# mcp23008.net
KiCad netlist of a schematic drawn in EAGLE
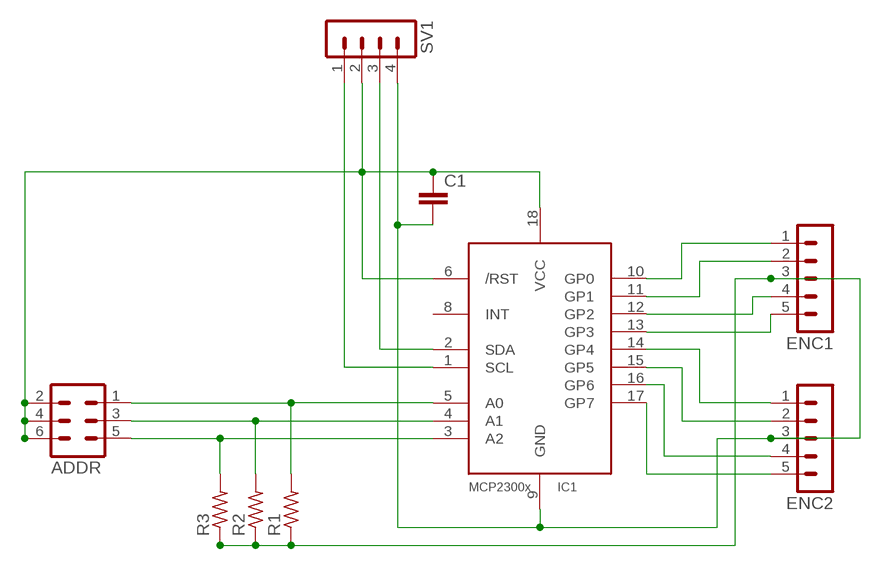
[diagram p0: schematic, sheet 1]

(export (version "E")
  (design (tool "Eeschema 10.0.6"))
  (components
    (comp (ref "ADDR")
      (value "MA03-2")
      (footprint "eagle-import:MA03-2")
      (libsource (lib "eagle-import") (part "MA03-2"))
    )
    (comp (ref "C1")
      (value "C2.5/2")
      (footprint "eagle-import:C2.5-2")
      (libsource (lib "eagle-import") (part "C2.5/2"))
    )
    (comp (ref "ENC1")
      (value "MA05-1")
      (footprint "eagle-import:MA05-1")
      (libsource (lib "eagle-import") (part "MA05-1"))
    )
    (comp (ref "ENC2")
      (value "MA05-1")
      (footprint "eagle-import:MA05-1")
      (libsource (lib "eagle-import") (part "MA05-1"))
    )
    (comp (ref "IC1")
      (value "MCP2300X/P")
      (footprint "eagle-import:DIL18")
      (libsource (lib "eagle-import") (part "MCP2300X/P"))
    )
    (comp (ref "R1")
      (value "R-US_0204/7")
      (footprint "eagle-import:0204_7")
      (libsource (lib "eagle-import") (part "R-US_0204/7"))
    )
    (comp (ref "R2")
      (value "R-US_0204/7")
      (footprint "eagle-import:0204_7")
      (libsource (lib "eagle-import") (part "R-US_0204/7"))
    )
    (comp (ref "R3")
      (value "R-US_0204/7")
      (footprint "eagle-import:0204_7")
      (libsource (lib "eagle-import") (part "R-US_0204/7"))
    )
    (comp (ref "SV1")
      (value "MA04-1")
      (footprint "eagle-import:MA04-1")
      (libsource (lib "eagle-import") (part "MA04-1"))
    )
  )
  (nets
    (net (code "1") (name "Net-(IC1-A0)") (class "Default")
      (node (ref "ADDR") (pin "1") (pinfunction "1_1") (pintype "passive"))
      (node (ref "IC1") (pin "5") (pinfunction "A0_5") (pintype "input"))
      (node (ref "R1") (pin "2") (pinfunction "2_2") (pintype "passive"))
    )
    (net (code "2") (name "Net-(IC1-A1)") (class "Default")
      (node (ref "ADDR") (pin "3") (pinfunction "3_3") (pintype "passive"))
      (node (ref "IC1") (pin "4") (pinfunction "A1_4") (pintype "input"))
      (node (ref "R2") (pin "2") (pinfunction "2_2") (pintype "passive"))
    )
    (net (code "3") (name "Net-(IC1-A2)") (class "Default")
      (node (ref "ADDR") (pin "5") (pinfunction "5_5") (pintype "passive"))
      (node (ref "IC1") (pin "3") (pinfunction "A2_3") (pintype "input"))
      (node (ref "R3") (pin "2") (pinfunction "2_2") (pintype "passive"))
    )
    (net (code "4") (name "Net-(IC1-GND)") (class "Default")
      (node (ref "C1") (pin "2") (pinfunction "2_2") (pintype "passive"))
      (node (ref "ENC1") (pin "3") (pinfunction "3_3") (pintype "passive"))
      (node (ref "ENC2") (pin "3") (pinfunction "3_3") (pintype "passive"))
      (node (ref "IC1") (pin "9") (pinfunction "GND_9") (pintype "power_in"))
      (node (ref "R1") (pin "1") (pinfunction "1_1") (pintype "passive"))
      (node (ref "R2") (pin "1") (pinfunction "1_1") (pintype "passive"))
      (node (ref "R3") (pin "1") (pinfunction "1_1") (pintype "passive"))
      (node (ref "SV1") (pin "4") (pinfunction "4_4") (pintype "passive"))
    )
    (net (code "5") (name "Net-(IC1-GP0)") (class "Default")
      (node (ref "ENC1") (pin "1") (pinfunction "1_1") (pintype "passive"))
      (node (ref "IC1") (pin "10") (pinfunction "GP0_10") (pintype "bidirectional"))
    )
    (net (code "6") (name "Net-(IC1-GP1)") (class "Default")
      (node (ref "ENC1") (pin "2") (pinfunction "2_2") (pintype "passive"))
      (node (ref "IC1") (pin "11") (pinfunction "GP1_11") (pintype "bidirectional"))
    )
    (net (code "7") (name "Net-(IC1-GP2)") (class "Default")
      (node (ref "ENC1") (pin "4") (pinfunction "4_4") (pintype "passive"))
      (node (ref "IC1") (pin "12") (pinfunction "GP2_12") (pintype "bidirectional"))
    )
    (net (code "8") (name "Net-(IC1-GP3)") (class "Default")
      (node (ref "ENC1") (pin "5") (pinfunction "5_5") (pintype "passive"))
      (node (ref "IC1") (pin "13") (pinfunction "GP3_13") (pintype "bidirectional"))
    )
    (net (code "9") (name "Net-(IC1-GP4)") (class "Default")
      (node (ref "ENC2") (pin "1") (pinfunction "1_1") (pintype "passive"))
      (node (ref "IC1") (pin "14") (pinfunction "GP4_14") (pintype "bidirectional"))
    )
    (net (code "10") (name "Net-(IC1-GP5)") (class "Default")
      (node (ref "ENC2") (pin "2") (pinfunction "2_2") (pintype "passive"))
      (node (ref "IC1") (pin "15") (pinfunction "GP5_15") (pintype "bidirectional"))
    )
    (net (code "11") (name "Net-(IC1-GP6)") (class "Default")
      (node (ref "ENC2") (pin "4") (pinfunction "4_4") (pintype "passive"))
      (node (ref "IC1") (pin "16") (pinfunction "GP6_16") (pintype "bidirectional"))
    )
    (net (code "12") (name "Net-(IC1-GP7)") (class "Default")
      (node (ref "ENC2") (pin "5") (pinfunction "5_5") (pintype "passive"))
      (node (ref "IC1") (pin "17") (pinfunction "GP7_17") (pintype "bidirectional"))
    )
    (net (code "13") (name "Net-(IC1-SCL)") (class "Default")
      (node (ref "IC1") (pin "1") (pinfunction "SCL_1") (pintype "bidirectional"))
      (node (ref "SV1") (pin "1") (pinfunction "1_1") (pintype "passive"))
    )
    (net (code "14") (name "Net-(IC1-SDA)") (class "Default")
      (node (ref "IC1") (pin "2") (pinfunction "SDA_2") (pintype "bidirectional"))
      (node (ref "SV1") (pin "3") (pinfunction "3_3") (pintype "passive"))
    )
    (net (code "15") (name "Net-(IC1-VCC)") (class "Default")
      (node (ref "ADDR") (pin "2") (pinfunction "2_2") (pintype "passive"))
      (node (ref "ADDR") (pin "4") (pinfunction "4_4") (pintype "passive"))
      (node (ref "ADDR") (pin "6") (pinfunction "6_6") (pintype "passive"))
      (node (ref "C1") (pin "1") (pinfunction "1_1") (pintype "passive"))
      (node (ref "IC1") (pin "18") (pinfunction "VCC_18") (pintype "power_in"))
      (node (ref "IC1") (pin "6") (pinfunction "/RST_6") (pintype "input"))
      (node (ref "SV1") (pin "2") (pinfunction "2_2") (pintype "passive"))
    )
    (net (code "16") (name "unconnected-(IC1-INT-Pad8)") (class "Default")
      (node (ref "IC1") (pin "8") (pinfunction "INT_8") (pintype "output"))
    )
  )
)
